# Rocket_Sensor_revM.net
KiCad netlist of a schematic drawn in EAGLE
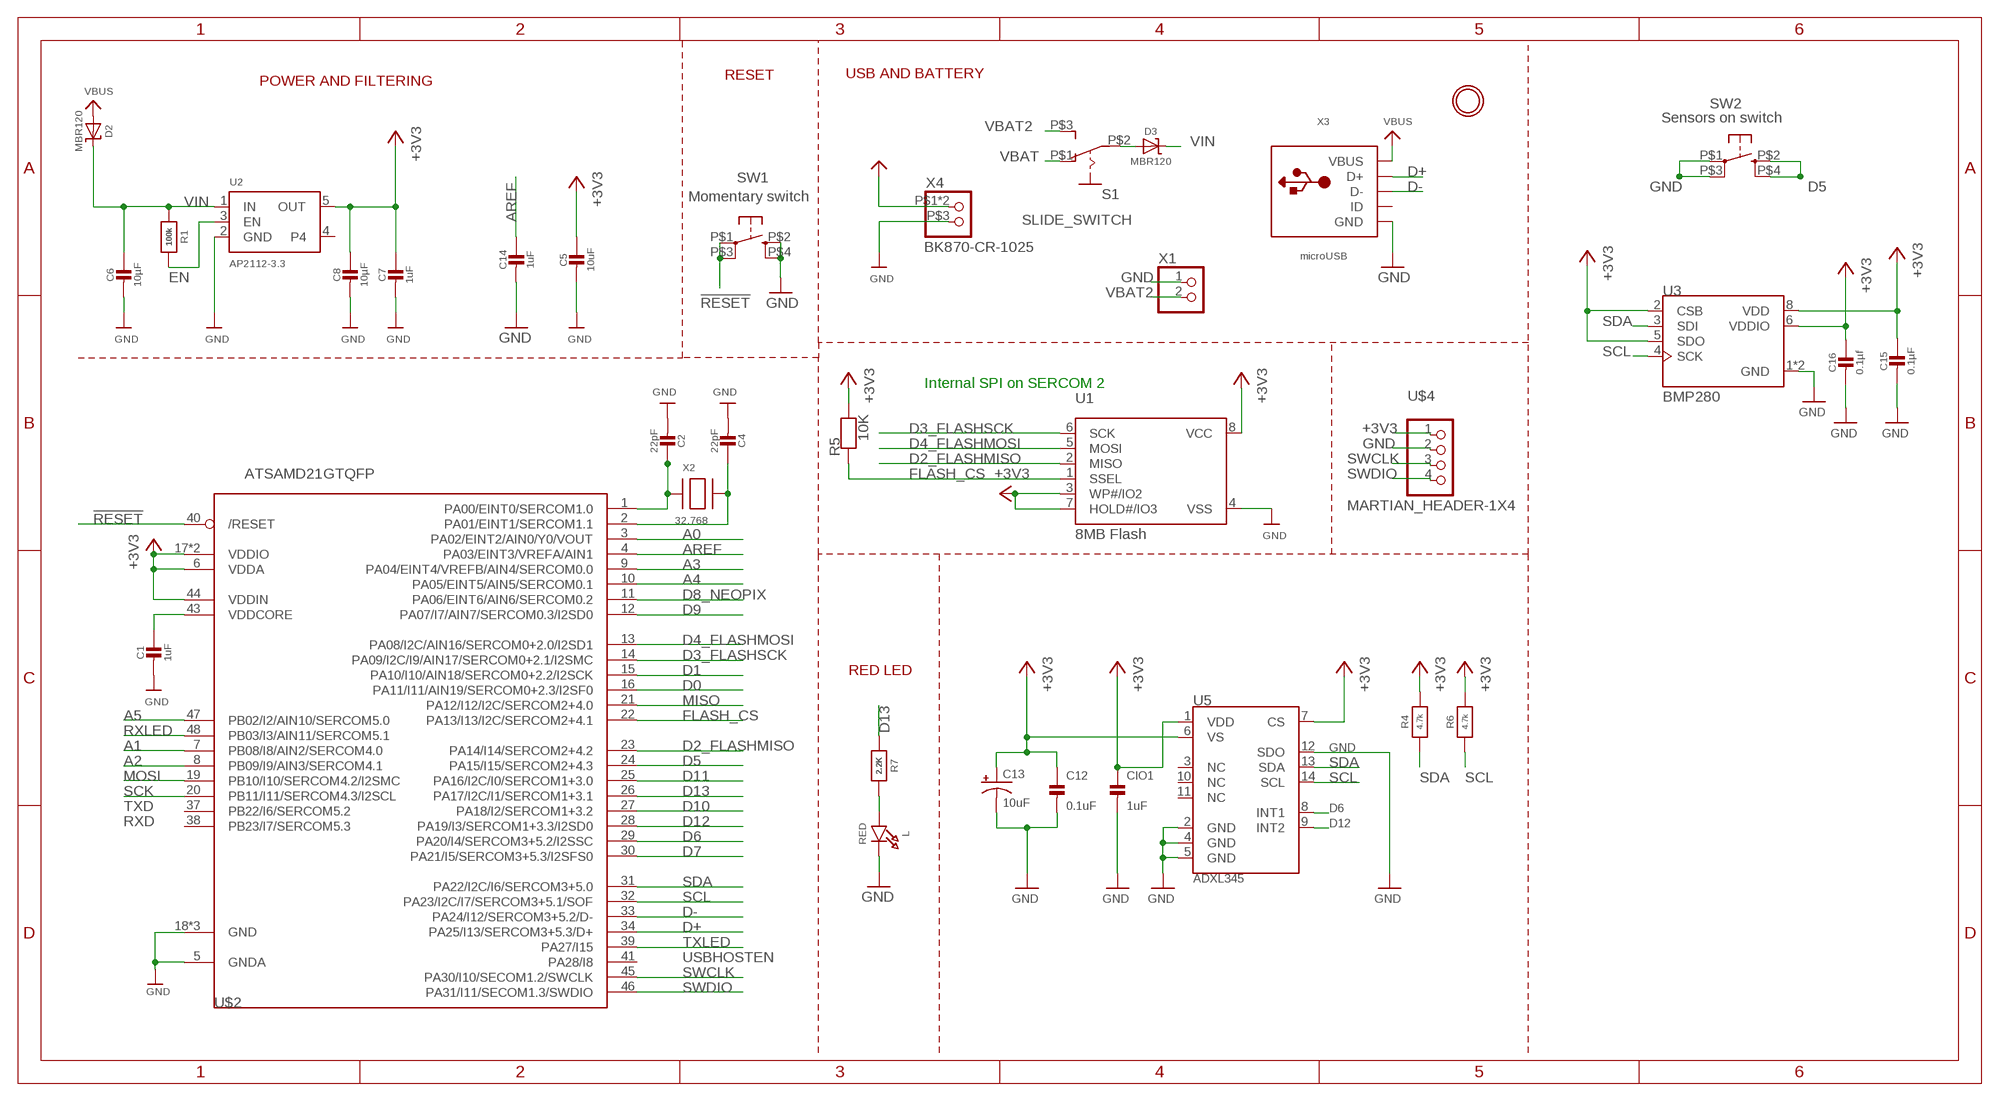
[diagram p0: schematic, sheet 1]

(export (version "E")
  (design (tool "Eeschema 10.0.6"))
  (components
    (comp (ref "C1")
      (value "1uF")
      (footprint "eagle-import:MICROBUILDER__1206")
      (libsource (lib "eagle-import") (part "MICROBUILDER_CAP_CERAMIC_1206"))
    )
    (comp (ref "C2")
      (value "22pF")
      (footprint "eagle-import:MICROBUILDER__1206")
      (libsource (lib "eagle-import") (part "MICROBUILDER_CAP_CERAMIC_1206"))
    )
    (comp (ref "C4")
      (value "22pF")
      (footprint "eagle-import:MICROBUILDER__1206")
      (libsource (lib "eagle-import") (part "MICROBUILDER_CAP_CERAMIC_1206"))
    )
    (comp (ref "C5")
      (value "10uF")
      (footprint "eagle-import:MICROBUILDER__1206")
      (libsource (lib "eagle-import") (part "MICROBUILDER_CAP_CERAMIC_1206"))
    )
    (comp (ref "C6")
      (value "10µF")
      (footprint "eagle-import:MICROBUILDER__1206")
      (libsource (lib "eagle-import") (part "MICROBUILDER_CAP_CERAMIC_1206"))
    )
    (comp (ref "C7")
      (value "1uF")
      (footprint "eagle-import:MICROBUILDER__1206")
      (libsource (lib "eagle-import") (part "MICROBUILDER_CAP_CERAMIC_1206"))
    )
    (comp (ref "C8")
      (value "10µF")
      (footprint "eagle-import:MICROBUILDER__1206")
      (libsource (lib "eagle-import") (part "MICROBUILDER_CAP_CERAMIC_1206"))
    )
    (comp (ref "C12")
      (value "0.1uF")
      (footprint "eagle-import:MICROBUILDER__1206")
      (libsource (lib "eagle-import") (part "MICROBUILDER_CAP_CERAMIC_1206"))
    )
    (comp (ref "C13")
      (value "10uF")
      (footprint "eagle-import:EIA3216")
      (libsource (lib "eagle-import") (part "10UF-POLAR-EIA3216-16V-10%(TANT)"))
    )
    (comp (ref "C14")
      (value "1uF")
      (footprint "eagle-import:MICROBUILDER__1206")
      (libsource (lib "eagle-import") (part "MICROBUILDER_CAP_CERAMIC_1206"))
    )
    (comp (ref "C15")
      (value "0.1µF")
      (footprint "eagle-import:MICROBUILDER__1206")
      (libsource (lib "eagle-import") (part "MICROBUILDER_CAP_CERAMIC_1206"))
    )
    (comp (ref "C16")
      (value "0.1µf")
      (footprint "eagle-import:MICROBUILDER__1206")
      (libsource (lib "eagle-import") (part "MICROBUILDER_CAP_CERAMIC_1206"))
    )
    (comp (ref "CIO1")
      (value "1uF")
      (footprint "eagle-import:MICROBUILDER__1206")
      (libsource (lib "eagle-import") (part "MICROBUILDER_CAP_CERAMIC_1206"))
    )
    (comp (ref "D2")
      (value "MBR120")
      (footprint "eagle-import:MICROBUILDER_SOD-123")
      (libsource (lib "eagle-import") (part "MICROBUILDER_DIODE-SCHOTTKYSOD-123"))
    )
    (comp (ref "D3")
      (value "MBR120")
      (footprint "eagle-import:MICROBUILDER_SOD-123")
      (libsource (lib "eagle-import") (part "MICROBUILDER_DIODE-SCHOTTKYSOD-123"))
    )
    (comp (ref "L")
      (value "RED")
      (footprint "eagle-import:MICROBUILDER_CHIPLED_1206")
      (libsource (lib "eagle-import") (part "MICROBUILDER_LED1206"))
    )
    (comp (ref "R1")
      (value "100k")
      (footprint "eagle-import:MICROBUILDER__0805")
      (libsource (lib "eagle-import") (part "MICROBUILDER_RESISTOR_0805"))
    )
    (comp (ref "R4")
      (value "4.7k")
      (footprint "eagle-import:MICROBUILDER__0805")
      (libsource (lib "eagle-import") (part "MICROBUILDER_RESISTOR_0805"))
    )
    (comp (ref "R5")
      (value "10K")
      (footprint "eagle-import:MICROBUILDER__0805")
      (libsource (lib "eagle-import") (part "MICROBUILDER_RESISTOR_0805"))
    )
    (comp (ref "R6")
      (value "4.7k")
      (footprint "eagle-import:MICROBUILDER__0805")
      (libsource (lib "eagle-import") (part "MICROBUILDER_RESISTOR_0805"))
    )
    (comp (ref "R7")
      (value "2.2K")
      (footprint "eagle-import:MICROBUILDER__0805")
      (libsource (lib "eagle-import") (part "MICROBUILDER_RESISTOR_0805"))
    )
    (comp (ref "S1")
      (value "SLIDE_SWITCH")
      (footprint "eagle-import:MSK12C02_SLIDE_SWITCH")
      (libsource (lib "eagle-import") (part "MSK12C02_SLIDE_SWITCH"))
    )
    (comp (ref "SW1")
      (value "Momentary switch")
      (footprint "eagle-import:ALIEXPRESS_WHITE_TACTILE_PUSHBUTTON")
      (libsource (lib "eagle-import") (part "ALIEXPRESS_WHITE_TACTILE_PUSHBUTTON"))
    )
    (comp (ref "SW2")
      (value "Sensors on switch")
      (footprint "eagle-import:ALIEXPRESS_WHITE_TACTILE_PUSHBUTTON")
      (libsource (lib "eagle-import") (part "ALIEXPRESS_WHITE_TACTILE_PUSHBUTTON"))
    )
    (comp (ref "U$2")
      (value "ATSAMD21GTQFP")
      (footprint "eagle-import:TQFP-48")
      (libsource (lib "eagle-import") (part "MICROBUILDER_ATSAMD21GTQFP"))
    )
    (comp (ref "U$4")
      (value "MARTIAN_HEADER-1X4")
      (footprint "eagle-import:MARTIAN_1X4_ROUND")
      (libsource (lib "eagle-import") (part "MARTIAN_HEADER-1X4"))
    )
    (comp (ref "U$7")
      (value "MICROBUILDER_MOUNTINGHOLE2.0")
      (footprint "eagle-import:MICROBUILDER_MOUNTINGHOLE_2.0_PLATED")
      (libsource (lib "eagle-import") (part "MICROBUILDER_MOUNTINGHOLE2.0"))
    )
    (comp (ref "U1")
      (value "8MB Flash")
      (footprint "eagle-import:MICROBUILDER_SOIC8_208MIL")
      (libsource (lib "eagle-import") (part "MICROBUILDER_SPIFLASH_SOIC8208MIL"))
    )
    (comp (ref "U2")
      (value "AP2112-3.3")
      (footprint "eagle-import:MICROBUILDER_SOT23-5")
      (libsource (lib "eagle-import") (part "MICROBUILDER_VREG_SOT23-5"))
    )
    (comp (ref "U3")
      (value "BMP280")
      (footprint "eagle-import:XDCR_BMP280")
      (fields (field (name "MF") "Bosch"))
      (libsource (lib "eagle-import") (part "BMP280"))
    )
    (comp (ref "U5")
      (value "ADXL345")
      (footprint "eagle-import:LGA-14")
      (libsource (lib "eagle-import") (part "ADXL345"))
    )
    (comp (ref "X1")
      (value "MICROBUILDER_CON_JST_PH_2PIN")
      (footprint "eagle-import:MICROBUILDER_JSTPH2")
      (libsource (lib "eagle-import") (part "MICROBUILDER_CON_JST_PH_2PIN"))
    )
    (comp (ref "X2")
      (value "32.768")
      (footprint "eagle-import:ADAFRUIT2_XTAL3215")
      (libsource (lib "eagle-import") (part "ADAFRUIT2_XTAL-3.2X1.5"))
    )
    (comp (ref "X3")
      (value "microUSB")
      (footprint "eagle-import:ALIEXPRESS_MICROUSB_RECEPTICLE_V2")
      (libsource (lib "eagle-import") (part "ALIEXPRESS_MICROUSB_RECEPTICLEV2"))
    )
    (comp (ref "X4")
      (value "BK870-CR-1025")
      (footprint "eagle-import:BK870-CR-1025_COIN_CELL_RETAINER")
      (libsource (lib "eagle-import") (part "BK870-CR-1025_COIN_CELL_RETAINER"))
    )
  )
  (nets
    (net (code "1") (name "+3V3") (class "Default")
      (node (ref "C12") (pin "1") (pinfunction "1_1") (pintype "passive"))
      (node (ref "C13") (pin "+") (pinfunction "+_+") (pintype "passive"))
      (node (ref "C15") (pin "1") (pinfunction "1_1") (pintype "passive"))
      (node (ref "C16") (pin "1") (pinfunction "1_1") (pintype "passive"))
      (node (ref "C5") (pin "1") (pinfunction "1_1") (pintype "passive"))
      (node (ref "C7") (pin "1") (pinfunction "1_1") (pintype "passive"))
      (node (ref "C8") (pin "1") (pinfunction "1_1") (pintype "passive"))
      (node (ref "CIO1") (pin "1") (pinfunction "1_1") (pintype "passive"))
      (node (ref "R4") (pin "2") (pinfunction "2_2") (pintype "passive"))
      (node (ref "R5") (pin "2") (pinfunction "2_2") (pintype "passive"))
      (node (ref "R6") (pin "2") (pinfunction "2_2") (pintype "passive"))
      (node (ref "U$2") (pin "17") (pinfunction "VDDIO_17") (pintype "power_in"))
      (node (ref "U$2") (pin "36") (pinfunction "VDDIO_36") (pintype "power_in"))
      (node (ref "U$2") (pin "44") (pinfunction "VDDIN_44") (pintype "power_in"))
      (node (ref "U$2") (pin "6") (pinfunction "VDDA_6") (pintype "power_in"))
      (node (ref "U$4") (pin "1") (pinfunction "9_1") (pintype "passive"))
      (node (ref "U1") (pin "3") (pinfunction "WP#/IO2_3") (pintype "bidirectional"))
      (node (ref "U1") (pin "7") (pinfunction "HOLD#/IO3_7") (pintype "bidirectional"))
      (node (ref "U1") (pin "8") (pinfunction "VCC_8") (pintype "bidirectional"))
      (node (ref "U2") (pin "5") (pinfunction "OUT_5") (pintype "power_in"))
      (node (ref "U3") (pin "2") (pinfunction "CSB_2") (pintype "input"))
      (node (ref "U3") (pin "5") (pinfunction "SDO_5") (pintype "bidirectional"))
      (node (ref "U3") (pin "6") (pinfunction "VDDIO_6") (pintype "power_in"))
      (node (ref "U3") (pin "8") (pinfunction "VDD_8") (pintype "power_in"))
      (node (ref "U5") (pin "1") (pinfunction "VDD_1") (pintype "bidirectional"))
      (node (ref "U5") (pin "6") (pinfunction "VS_6") (pintype "bidirectional"))
      (node (ref "U5") (pin "7") (pinfunction "CS_7") (pintype "bidirectional"))
    )
    (net (code "2") (name "/A0") (class "Default")
      (node (ref "U$2") (pin "3") (pinfunction "PA02/EINT2/AIN0/Y0/VOUT_3") (pintype "bidirectional"))
    )
    (net (code "3") (name "/A1") (class "Default")
      (node (ref "U$2") (pin "7") (pinfunction "PB08/I8/AIN2/SERCOM4.0_7") (pintype "bidirectional"))
    )
    (net (code "4") (name "/A2") (class "Default")
      (node (ref "U$2") (pin "8") (pinfunction "PB09/I9/AIN3/SERCOM4.1_8") (pintype "bidirectional"))
    )
    (net (code "5") (name "/A3") (class "Default")
      (node (ref "U$2") (pin "9") (pinfunction "PA04/EINT4/VREFB/AIN4/SERCOM0.0_9") (pintype "bidirectional"))
    )
    (net (code "6") (name "/A4") (class "Default")
      (node (ref "U$2") (pin "10") (pinfunction "PA05/EINT5/AIN5/SERCOM0.1_10") (pintype "bidirectional"))
    )
    (net (code "7") (name "/A5") (class "Default")
      (node (ref "U$2") (pin "47") (pinfunction "PB02/I2/AIN10/SERCOM5.0_47") (pintype "bidirectional"))
    )
    (net (code "8") (name "/AREF") (class "Default")
      (node (ref "C14") (pin "1") (pinfunction "1_1") (pintype "passive"))
      (node (ref "U$2") (pin "4") (pinfunction "PA03/EINT3/VREFA/AIN1_4") (pintype "bidirectional"))
    )
    (net (code "9") (name "/D+") (class "Default")
      (node (ref "U$2") (pin "34") (pinfunction "PA25/I13/SERCOM3+5.3/D+_34") (pintype "bidirectional"))
      (node (ref "X3") (pin "D+") (pinfunction "D+_D+") (pintype "bidirectional"))
    )
    (net (code "10") (name "/D-") (class "Default")
      (node (ref "U$2") (pin "33") (pinfunction "PA24/I12/SERCOM3+5.2/D-_33") (pintype "bidirectional"))
      (node (ref "X3") (pin "D-") (pinfunction "D-_D-") (pintype "bidirectional"))
    )
    (net (code "11") (name "/D0") (class "Default")
      (node (ref "U$2") (pin "16") (pinfunction "PA11/I11/AIN19/SERCOM0+2.3/I2SF0_16") (pintype "bidirectional"))
    )
    (net (code "12") (name "/D1") (class "Default")
      (node (ref "U$2") (pin "15") (pinfunction "PA10/I10/AIN18/SERCOM0+2.2/I2SCK_15") (pintype "bidirectional"))
    )
    (net (code "13") (name "/D2_FLASHMISO") (class "Default")
      (node (ref "U$2") (pin "23") (pinfunction "PA14/I14/SERCOM2+4.2_23") (pintype "bidirectional"))
      (node (ref "U1") (pin "2") (pinfunction "MISO_2") (pintype "bidirectional"))
    )
    (net (code "14") (name "/D3_FLASHSCK") (class "Default")
      (node (ref "U$2") (pin "14") (pinfunction "PA09/I2C/I9/AIN17/SERCOM0+2.1/I2SMC_14") (pintype "bidirectional"))
      (node (ref "U1") (pin "6") (pinfunction "SCK_6") (pintype "bidirectional"))
    )
    (net (code "15") (name "/D4_FLASHMOSI") (class "Default")
      (node (ref "U$2") (pin "13") (pinfunction "PA08/I2C/AIN16/SERCOM0+2.0/I2SD1_13") (pintype "bidirectional"))
      (node (ref "U1") (pin "5") (pinfunction "MOSI_5") (pintype "bidirectional"))
    )
    (net (code "16") (name "/D5") (class "Default")
      (node (ref "SW2") (pin "P$2") (pinfunction "S_P$2") (pintype "passive"))
      (node (ref "SW2") (pin "P$4") (pinfunction "S1_P$4") (pintype "passive"))
      (node (ref "U$2") (pin "24") (pinfunction "PA15/I15/SERCOM2+4.3_24") (pintype "bidirectional"))
    )
    (net (code "17") (name "/D6") (class "Default")
      (node (ref "U$2") (pin "29") (pinfunction "PA20/I4/SERCOM3+5.2/I2SSC_29") (pintype "bidirectional"))
      (node (ref "U5") (pin "8") (pinfunction "INT1_8") (pintype "bidirectional"))
    )
    (net (code "18") (name "/D7") (class "Default")
      (node (ref "U$2") (pin "30") (pinfunction "PA21/I5/SERCOM3+5.3/I2SFS0_30") (pintype "bidirectional"))
    )
    (net (code "19") (name "/D8_NEOPIX") (class "Default")
      (node (ref "U$2") (pin "11") (pinfunction "PA06/EINT6/AIN6/SERCOM0.2_11") (pintype "bidirectional"))
    )
    (net (code "20") (name "/D9") (class "Default")
      (node (ref "U$2") (pin "12") (pinfunction "PA07/I7/AIN7/SERCOM0.3/I2SD0_12") (pintype "bidirectional"))
    )
    (net (code "21") (name "/D10") (class "Default")
      (node (ref "U$2") (pin "27") (pinfunction "PA18/I2/SERCOM1+3.2_27") (pintype "bidirectional"))
    )
    (net (code "22") (name "/D11") (class "Default")
      (node (ref "U$2") (pin "25") (pinfunction "PA16/I2C/I0/SERCOM1+3.0_25") (pintype "bidirectional"))
    )
    (net (code "23") (name "/D12") (class "Default")
      (node (ref "U$2") (pin "28") (pinfunction "PA19/I3/SERCOM1+3.3/I2SD0_28") (pintype "bidirectional"))
      (node (ref "U5") (pin "9") (pinfunction "INT2_9") (pintype "bidirectional"))
    )
    (net (code "24") (name "/D13") (class "Default")
      (node (ref "R7") (pin "1") (pinfunction "1_1") (pintype "passive"))
      (node (ref "U$2") (pin "26") (pinfunction "PA17/I2C/I1/SERCOM1+3.1_26") (pintype "bidirectional"))
    )
    (net (code "25") (name "/EN") (class "Default")
      (node (ref "R1") (pin "2") (pinfunction "2_2") (pintype "passive"))
      (node (ref "U2") (pin "3") (pinfunction "EN_3") (pintype "input"))
    )
    (net (code "26") (name "/FLASH_CS") (class "Default")
      (node (ref "R5") (pin "1") (pinfunction "1_1") (pintype "passive"))
      (node (ref "U$2") (pin "22") (pinfunction "PA13/I13/I2C/SERCOM2+4.1_22") (pintype "bidirectional"))
      (node (ref "U1") (pin "1") (pinfunction "SSEL_1") (pintype "bidirectional"))
    )
    (net (code "27") (name "/MISO") (class "Default")
      (node (ref "U$2") (pin "21") (pinfunction "PA12/I12/I2C/SERCOM2+4.0_21") (pintype "bidirectional"))
    )
    (net (code "28") (name "/MOSI") (class "Default")
      (node (ref "U$2") (pin "19") (pinfunction "PB10/I10/SERCOM4.2/I2SMC_19") (pintype "bidirectional"))
    )
    (net (code "29") (name "/RXLED") (class "Default")
      (node (ref "U$2") (pin "48") (pinfunction "PB03/I3/AIN11/SERCOM5.1_48") (pintype "bidirectional"))
    )
    (net (code "30") (name "/SCK") (class "Default")
      (node (ref "U$2") (pin "20") (pinfunction "PB11/I11/SERCOM4.3/I2SCL_20") (pintype "bidirectional"))
    )
    (net (code "31") (name "/SCL") (class "Default")
      (node (ref "R6") (pin "1") (pinfunction "1_1") (pintype "passive"))
      (node (ref "U$2") (pin "32") (pinfunction "PA23/I2C/I7/SERCOM3+5.1/SOF_32") (pintype "bidirectional"))
      (node (ref "U3") (pin "4") (pinfunction "SCK_4") (pintype "input"))
      (node (ref "U5") (pin "14") (pinfunction "SCL_14") (pintype "bidirectional"))
    )
    (net (code "32") (name "/SDA") (class "Default")
      (node (ref "R4") (pin "1") (pinfunction "1_1") (pintype "passive"))
      (node (ref "U$2") (pin "31") (pinfunction "PA22/I2C/I6/SERCOM3+5.0_31") (pintype "bidirectional"))
      (node (ref "U3") (pin "3") (pinfunction "SDI_3") (pintype "bidirectional"))
      (node (ref "U5") (pin "13") (pinfunction "SDA_13") (pintype "bidirectional"))
    )
    (net (code "33") (name "/SWCLK") (class "Default")
      (node (ref "U$2") (pin "45") (pinfunction "PA30/I10/SECOM1.2/SWCLK_45") (pintype "bidirectional"))
      (node (ref "U$4") (pin "3") (pinfunction "11_3") (pintype "passive"))
    )
    (net (code "34") (name "/SWDIO") (class "Default")
      (node (ref "U$2") (pin "46") (pinfunction "PA31/I11/SECOM1.3/SWDIO_46") (pintype "bidirectional"))
      (node (ref "U$4") (pin "4") (pinfunction "12_4") (pintype "passive"))
    )
    (net (code "35") (name "/TXLED") (class "Default")
      (node (ref "U$2") (pin "39") (pinfunction "PA27/I15_39") (pintype "bidirectional"))
    )
    (net (code "36") (name "/VBAT2") (class "Default")
      (node (ref "S1") (pin "P$3") (pinfunction "S_P$3") (pintype "passive"))
      (node (ref "X1") (pin "2") (pinfunction "2_2") (pintype "passive"))
    )
    (net (code "37") (name "/VIN") (class "Default")
      (node (ref "C6") (pin "1") (pinfunction "1_1") (pintype "passive"))
      (node (ref "D2") (pin "C") (pinfunction "C_C") (pintype "passive"))
      (node (ref "D3") (pin "C") (pinfunction "C_C") (pintype "passive"))
      (node (ref "R1") (pin "1") (pinfunction "1_1") (pintype "passive"))
      (node (ref "U2") (pin "1") (pinfunction "IN_1") (pintype "power_in"))
    )
    (net (code "38") (name "/~{RESET}") (class "Default")
      (node (ref "SW1") (pin "P$1") (pinfunction "P_P$1") (pintype "passive"))
      (node (ref "SW1") (pin "P$3") (pinfunction "P1_P$3") (pintype "passive"))
      (node (ref "U$2") (pin "40") (pinfunction "/RESET_40") (pintype "bidirectional"))
    )
    (net (code "39") (name "GND") (class "Default")
      (node (ref "C1") (pin "2") (pinfunction "2_2") (pintype "passive"))
      (node (ref "C12") (pin "2") (pinfunction "2_2") (pintype "passive"))
      (node (ref "C13") (pin "-") (pinfunction "-_-") (pintype "passive"))
      (node (ref "C14") (pin "2") (pinfunction "2_2") (pintype "passive"))
      (node (ref "C15") (pin "2") (pinfunction "2_2") (pintype "passive"))
      (node (ref "C16") (pin "2") (pinfunction "2_2") (pintype "passive"))
      (node (ref "C2") (pin "2") (pinfunction "2_2") (pintype "passive"))
      (node (ref "C4") (pin "2") (pinfunction "2_2") (pintype "passive"))
      (node (ref "C5") (pin "2") (pinfunction "2_2") (pintype "passive"))
      (node (ref "C6") (pin "2") (pinfunction "2_2") (pintype "passive"))
      (node (ref "C7") (pin "2") (pinfunction "2_2") (pintype "passive"))
      (node (ref "C8") (pin "2") (pinfunction "2_2") (pintype "passive"))
      (node (ref "CIO1") (pin "2") (pinfunction "2_2") (pintype "passive"))
      (node (ref "L") (pin "C") (pinfunction "C_C") (pintype "passive"))
      (node (ref "SW1") (pin "P$2") (pinfunction "S_P$2") (pintype "passive"))
      (node (ref "SW1") (pin "P$4") (pinfunction "S1_P$4") (pintype "passive"))
      (node (ref "SW2") (pin "P$1") (pinfunction "P_P$1") (pintype "passive"))
      (node (ref "SW2") (pin "P$3") (pinfunction "P1_P$3") (pintype "passive"))
      (node (ref "U$2") (pin "18") (pinfunction "GND_18") (pintype "power_in"))
      (node (ref "U$2") (pin "35") (pinfunction "GND_35") (pintype "power_in"))
      (node (ref "U$2") (pin "42") (pinfunction "GND_42") (pintype "power_in"))
      (node (ref "U$2") (pin "5") (pinfunction "GNDA_5") (pintype "power_in"))
      (node (ref "U$4") (pin "2") (pinfunction "10_2") (pintype "passive"))
      (node (ref "U1") (pin "4") (pinfunction "VSS_4") (pintype "bidirectional"))
      (node (ref "U2") (pin "2") (pinfunction "GND_2") (pintype "power_in"))
      (node (ref "U3") (pin "1") (pinfunction "GND_1") (pintype "power_in"))
      (node (ref "U3") (pin "7") (pinfunction "GND_7") (pintype "power_in"))
      (node (ref "U5") (pin "12") (pinfunction "SDO_12") (pintype "bidirectional"))
      (node (ref "U5") (pin "2") (pinfunction "GND_2") (pintype "bidirectional"))
      (node (ref "U5") (pin "4") (pinfunction "GND_4") (pintype "bidirectional"))
      (node (ref "U5") (pin "5") (pinfunction "GND_5") (pintype "bidirectional"))
      (node (ref "X1") (pin "1") (pinfunction "1_1") (pintype "passive"))
      (node (ref "X3") (pin "GND") (pinfunction "GND_GND") (pintype "power_in"))
      (node (ref "X3") (pin "P$6") (pinfunction "GND_P$6") (pintype "power_in"))
      (node (ref "X3") (pin "P$7") (pinfunction "GND_P$7") (pintype "power_in"))
      (node (ref "X3") (pin "P$8") (pinfunction "GND_P$8") (pintype "power_in"))
      (node (ref "X3") (pin "P$9") (pinfunction "GND_P$9") (pintype "power_in"))
      (node (ref "X4") (pin "P$3") (pinfunction "GND_P$3") (pintype "passive"))
    )
    (net (code "40") (name "Net-(L-PadA)") (class "Default")
      (node (ref "L") (pin "A") (pinfunction "A_A") (pintype "passive"))
      (node (ref "R7") (pin "2") (pinfunction "2_2") (pintype "passive"))
    )
    (net (code "41") (name "Net-(S1-P)") (class "Default")
      (node (ref "D3") (pin "A") (pinfunction "A_A") (pintype "passive"))
      (node (ref "S1") (pin "P$2") (pinfunction "P_P$2") (pintype "passive"))
    )
    (net (code "42") (name "Net-(U$2-PA00{slash}EINT0{slash}SERCOM1.0)") (class "Default")
      (node (ref "C2") (pin "1") (pinfunction "1_1") (pintype "passive"))
      (node (ref "U$2") (pin "1") (pinfunction "PA00/EINT0/SERCOM1.0_1") (pintype "bidirectional"))
      (node (ref "X2") (pin "P$1") (pinfunction "P$1_P$1") (pintype "bidirectional"))
    )
    (net (code "43") (name "Net-(U$2-PA01{slash}EINT1{slash}SERCOM1.1)") (class "Default")
      (node (ref "C4") (pin "1") (pinfunction "1_1") (pintype "passive"))
      (node (ref "U$2") (pin "2") (pinfunction "PA01/EINT1/SERCOM1.1_2") (pintype "bidirectional"))
      (node (ref "X2") (pin "P$2") (pinfunction "P$2_P$2") (pintype "bidirectional"))
    )
    (net (code "44") (name "Net-(U$2-VDDCORE)") (class "Default")
      (node (ref "C1") (pin "1") (pinfunction "1_1") (pintype "passive"))
      (node (ref "U$2") (pin "43") (pinfunction "VDDCORE_43") (pintype "power_in"))
    )
    (net (code "45") (name "VBAT") (class "Default")
      (node (ref "S1") (pin "P$1") (pinfunction "O_P$1") (pintype "passive"))
      (node (ref "X4") (pin "P$1") (pinfunction "VBAT_P$1") (pintype "passive"))
      (node (ref "X4") (pin "P$2") (pinfunction "VBAT_P$2") (pintype "passive"))
    )
    (net (code "46") (name "VBUS") (class "Default")
      (node (ref "D2") (pin "A") (pinfunction "A_A") (pintype "passive"))
      (node (ref "X3") (pin "VBUS") (pinfunction "VBUS_VBUS") (pintype "power_in"))
    )
    (net (code "47") (name "unconnected-(U$2-PA28{slash}I8-Pad41)") (class "Default")
      (node (ref "U$2") (pin "41") (pinfunction "PA28/I8_41") (pintype "bidirectional"))
    )
    (net (code "48") (name "unconnected-(U$2-PB22{slash}I6{slash}SERCOM5.2-Pad37)") (class "Default")
      (node (ref "U$2") (pin "37") (pinfunction "PB22/I6/SERCOM5.2_37") (pintype "bidirectional"))
    )
    (net (code "49") (name "unconnected-(U$2-PB23{slash}I7{slash}SERCOM5.3-Pad38)") (class "Default")
      (node (ref "U$2") (pin "38") (pinfunction "PB23/I7/SERCOM5.3_38") (pintype "bidirectional"))
    )
    (net (code "50") (name "unconnected-(U2-P4-Pad4)") (class "Default")
      (node (ref "U2") (pin "4") (pinfunction "P4_4") (pintype "bidirectional"))
    )
    (net (code "51") (name "unconnected-(U5-NC-Pad3)") (class "Default")
      (node (ref "U5") (pin "3") (pinfunction "NC_3") (pintype "bidirectional"))
    )
    (net (code "52") (name "unconnected-(U5-NC-Pad10)") (class "Default")
      (node (ref "U5") (pin "10") (pinfunction "NC_10") (pintype "bidirectional"))
    )
    (net (code "53") (name "unconnected-(U5-NC-Pad11)") (class "Default")
      (node (ref "U5") (pin "11") (pinfunction "NC_11") (pintype "bidirectional"))
    )
    (net (code "54") (name "unconnected-(X3-PadID)") (class "Default")
      (node (ref "X3") (pin "ID") (pinfunction "ID_ID") (pintype "bidirectional"))
    )
  )
)
